# 05_-_MCU.net
KiCad netlist of a schematic drawn in Altium Designer
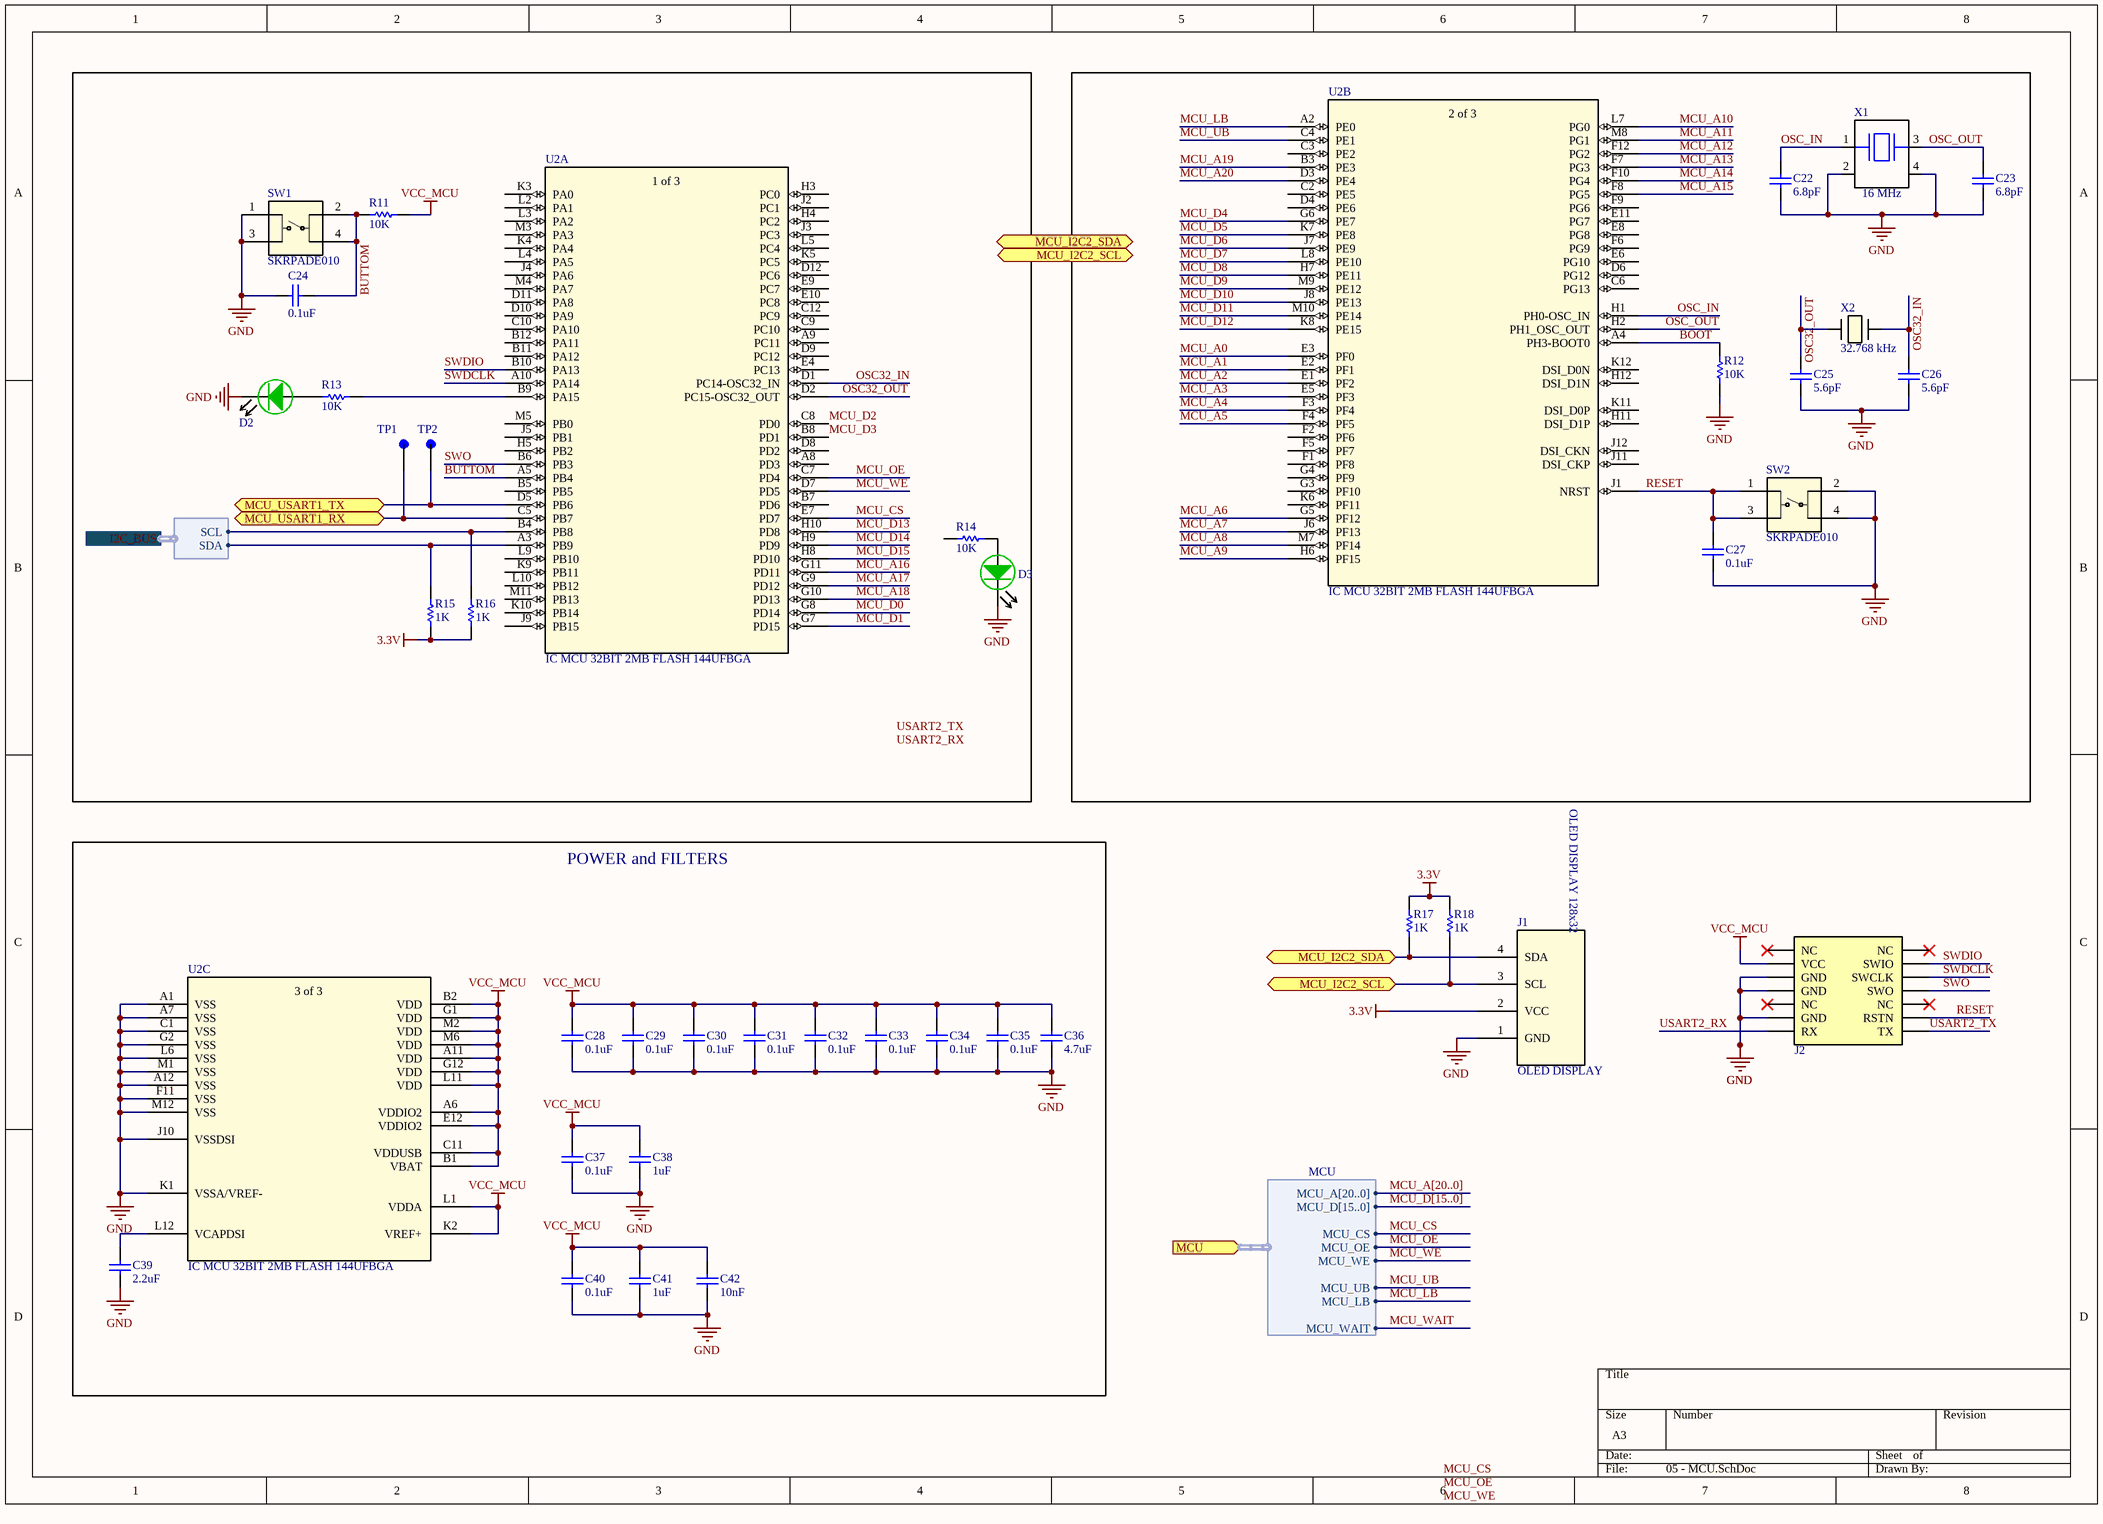
[diagram p0: 05 - MCU.SchDoc]

(export (version "E")
  (design (tool "Eeschema 10.0.6"))
  (components
    (comp (ref "C22")
      (value "6.8pF")
      (footprint "0402-C-R")
      (description "6.8 pF ±0.25pF 25V Ceramic Capacitor C0G, NP0 01005 (0402 Metric)")
      (fields (field (name "VOLTAGE") "25V") (field (name "TOLERANCE") "5%"))
      (libsource (lib "Schlib") (part "CAP CER 6.8PF 25V C0G/NP0 01005"))
    )
    (comp (ref "C23")
      (value "6.8pF")
      (footprint "0402-C-R")
      (description "6.8 pF ±0.25pF 25V Ceramic Capacitor C0G, NP0 01005 (0402 Metric)")
      (fields (field (name "VOLTAGE") "25V") (field (name "TOLERANCE") "5%"))
      (libsource (lib "Schlib") (part "CAP CER 6.8PF 25V C0G/NP0 01005"))
    )
    (comp (ref "C24")
      (value "0.1uF")
      (footprint "0402-C-R")
      (description "0.1 µF ±10% 25V Ceramic Capacitor X5R 0402 (1005 Metric)")
      (fields (field (name "VOLTAGE") "25V") (field (name "TOLERANCE") "10%"))
      (libsource (lib "Schlib") (part "CAP CER 0.1UF 25V X5R 0402"))
    )
    (comp (ref "C25")
      (value "5.6pF")
      (footprint "0402-C-R")
      (description "5.6 pF ±0.1pF 50V Ceramic Capacitor C0G, NP0 0402 (1005 Metric)")
      (fields (field (name "VOLTAGE") "50V") (field (name "TOLERANCE") "1%"))
      (libsource (lib "Schlib") (part "CAP CER 5.6PF 50V C0G/NPO 0402"))
    )
    (comp (ref "C26")
      (value "5.6pF")
      (footprint "0402-C-R")
      (description "5.6 pF ±0.1pF 50V Ceramic Capacitor C0G, NP0 0402 (1005 Metric)")
      (fields (field (name "VOLTAGE") "50V") (field (name "TOLERANCE") "1%"))
      (libsource (lib "Schlib") (part "CAP CER 5.6PF 50V C0G/NPO 0402"))
    )
    (comp (ref "C27")
      (value "0.1uF")
      (footprint "0402-C-R")
      (description "0.1 µF ±10% 25V Ceramic Capacitor X5R 0402 (1005 Metric)")
      (fields (field (name "VOLTAGE") "25V") (field (name "TOLERANCE") "10%"))
      (libsource (lib "Schlib") (part "CAP CER 0.1UF 25V X5R 0402"))
    )
    (comp (ref "C28")
      (value "0.1uF")
      (footprint "0402-C-R")
      (description "0.1 µF ±10% 25V Ceramic Capacitor X5R 0402 (1005 Metric)")
      (fields (field (name "VOLTAGE") "25V") (field (name "TOLERANCE") "10%"))
      (libsource (lib "Schlib") (part "CAP CER 0.1UF 25V X5R 0402"))
    )
    (comp (ref "C29")
      (value "0.1uF")
      (footprint "0402-C-R")
      (description "0.1 µF ±10% 25V Ceramic Capacitor X5R 0402 (1005 Metric)")
      (fields (field (name "VOLTAGE") "25V") (field (name "TOLERANCE") "10%"))
      (libsource (lib "Schlib") (part "CAP CER 0.1UF 25V X5R 0402"))
    )
    (comp (ref "C30")
      (value "0.1uF")
      (footprint "0402-C-R")
      (description "0.1 µF ±10% 25V Ceramic Capacitor X5R 0402 (1005 Metric)")
      (fields (field (name "VOLTAGE") "25V") (field (name "TOLERANCE") "10%"))
      (libsource (lib "Schlib") (part "CAP CER 0.1UF 25V X5R 0402"))
    )
    (comp (ref "C31")
      (value "0.1uF")
      (footprint "0402-C-R")
      (description "0.1 µF ±10% 25V Ceramic Capacitor X5R 0402 (1005 Metric)")
      (fields (field (name "VOLTAGE") "25V") (field (name "TOLERANCE") "10%"))
      (libsource (lib "Schlib") (part "CAP CER 0.1UF 25V X5R 0402"))
    )
    (comp (ref "C32")
      (value "0.1uF")
      (footprint "0402-C-R")
      (description "0.1 µF ±10% 25V Ceramic Capacitor X5R 0402 (1005 Metric)")
      (fields (field (name "VOLTAGE") "25V") (field (name "TOLERANCE") "10%"))
      (libsource (lib "Schlib") (part "CAP CER 0.1UF 25V X5R 0402"))
    )
    (comp (ref "C33")
      (value "0.1uF")
      (footprint "0402-C-R")
      (description "0.1 µF ±10% 25V Ceramic Capacitor X5R 0402 (1005 Metric)")
      (fields (field (name "VOLTAGE") "25V") (field (name "TOLERANCE") "10%"))
      (libsource (lib "Schlib") (part "CAP CER 0.1UF 25V X5R 0402"))
    )
    (comp (ref "C34")
      (value "0.1uF")
      (footprint "0402-C-R")
      (description "0.1 µF ±10% 25V Ceramic Capacitor X5R 0402 (1005 Metric)")
      (fields (field (name "VOLTAGE") "25V") (field (name "TOLERANCE") "10%"))
      (libsource (lib "Schlib") (part "CAP CER 0.1UF 25V X5R 0402"))
    )
    (comp (ref "C35")
      (value "0.1uF")
      (footprint "0402-C-R")
      (description "0.1 µF ±10% 25V Ceramic Capacitor X5R 0402 (1005 Metric)")
      (fields (field (name "VOLTAGE") "25V") (field (name "TOLERANCE") "10%"))
      (libsource (lib "Schlib") (part "CAP CER 0.1UF 25V X5R 0402"))
    )
    (comp (ref "C36")
      (value "4.7uF")
      (footprint "0402-C-R")
      (description "CAP SMD 0402 MLCC GERAL 4.7uF 25V ±20% 0402 X5s PN: GRM155D81C475ME15J MURATA")
      (fields (field (name "VOLTAGE") "25V") (field (name "TOLERANCE") "20%"))
      (libsource (lib "Schlib") (part "CAP CER 4.7UF 25V X5R 0402"))
    )
    (comp (ref "C37")
      (value "0.1uF")
      (footprint "0402-C-R")
      (description "0.1 µF ±10% 25V Ceramic Capacitor X5R 0402 (1005 Metric)")
      (fields (field (name "VOLTAGE") "25V") (field (name "TOLERANCE") "10%"))
      (libsource (lib "Schlib") (part "CAP CER 0.1UF 25V X5R 0402"))
    )
    (comp (ref "C38")
      (value "1uF")
      (footprint "0402-C-R")
      (description "1 µF ±10% 6.3V Ceramic Capacitor X5R 0402 (1005 Metric)")
      (fields (field (name "VOLTAGE") "6.3V") (field (name "TOLERANCE") "10%"))
      (libsource (lib "Schlib") (part "CAP CER 1UF 6.3V X5R 0402"))
    )
    (comp (ref "C39")
      (value "2.2uF")
      (footprint "0402-C-R")
      (description "2.2 µF ±20% 10V Ceramic Capacitor X5R 0402 (1005 Metric)")
      (fields (field (name "VOLTAGE") "10V") (field (name "TOLERANCE") "20%"))
      (libsource (lib "Schlib") (part "CAP CER 2.2UF 10V X5R 0402"))
    )
    (comp (ref "C40")
      (value "0.1uF")
      (footprint "0402-C-R")
      (description "0.1 µF ±10% 25V Ceramic Capacitor X5R 0402 (1005 Metric)")
      (fields (field (name "VOLTAGE") "25V") (field (name "TOLERANCE") "10%"))
      (libsource (lib "Schlib") (part "CAP CER 0.1UF 25V X5R 0402"))
    )
    (comp (ref "C41")
      (value "1uF")
      (footprint "0402-C-R")
      (description "1 µF ±10% 6.3V Ceramic Capacitor X5R 0402 (1005 Metric)")
      (fields (field (name "VOLTAGE") "6.3V") (field (name "TOLERANCE") "10%"))
      (libsource (lib "Schlib") (part "CAP CER 1UF 6.3V X5R 0402"))
    )
    (comp (ref "C42")
      (value "10nF")
      (footprint "0402-C-R")
      (description "10000 pF ±10% 25V Ceramic Capacitor X7R 0402 (1005 Metric)")
      (fields (field (name "VOLTAGE") "25V") (field (name "TOLERANCE") "10%"))
      (libsource (lib "Schlib") (part "CAP CER 10nF 25V X7R 0402"))
    )
    (comp (ref "D2")
      (value "150060GS75000")
      (footprint "LED0603")
      (description "LED SMD VD ALTO BRILHO 1,6x0,8x0,8mm 430mcd PN:150060GS75000 0603 WURTH")
      (libsource (lib "Schlib") (part "LED SMD VD 0603"))
    )
    (comp (ref "D3")
      (value "150060GS75000")
      (footprint "LED0603")
      (description "LED SMD VD ALTO BRILHO 1,6x0,8x0,8mm 430mcd PN:150060GS75000 0603 WURTH")
      (libsource (lib "Schlib") (part "LED SMD VD 0603"))
    )
    (comp (ref "J1")
      (value "OLED DISPLAY")
      (footprint "OLED_DISPLAY")
      (libsource (lib "Schlib") (part "OLED DISPLAY"))
    )
    (comp (ref "J2")
      (value "CONN HEADER SMD 14POS 1.27MM_1")
      (footprint "SAMTEC_FTSH-107-01-L-DV-K-A")
      (description "CONN HEADER SMD 14POS 1.27MM PN: FTSH-107-01-L-DV-K-A")
      (fields (field (name "MF") "Samtec Inc."))
      (libsource (lib "Schlib") (part "CONN HEADER SMD 14POS 1.27MM_1"))
    )
    (comp (ref "R11")
      (value "10K")
      (footprint "0402-R-R")
      (description "10 kOhms ±1% 0,063W, 1/16W Resistor de chip 0402 (métrico 1005) Resistente à umidade Filme grosso")
      (fields (field (name "POWER") "0.063W") (field (name "TOLERANCE") "1%"))
      (libsource (lib "Schlib") (part "RES 10K OHM 1% 1/16W 0402"))
    )
    (comp (ref "R12")
      (value "10K")
      (footprint "0402-R-R")
      (description "10 kOhms ±1% 0,063W, 1/16W Resistor de chip 0402 (métrico 1005) Resistente à umidade Filme grosso")
      (fields (field (name "POWER") "0.063W") (field (name "TOLERANCE") "1%"))
      (libsource (lib "Schlib") (part "RES 10K OHM 1% 1/16W 0402"))
    )
    (comp (ref "R13")
      (value "10K")
      (footprint "0402-R-R")
      (description "10 kOhms ±1% 0,063W, 1/16W Resistor de chip 0402 (métrico 1005) Resistente à umidade Filme grosso")
      (fields (field (name "POWER") "0.063W") (field (name "TOLERANCE") "1%"))
      (libsource (lib "Schlib") (part "RES 10K OHM 1% 1/16W 0402"))
    )
    (comp (ref "R14")
      (value "10K")
      (footprint "0402-R-R")
      (description "10 kOhms ±1% 0,063W, 1/16W Resistor de chip 0402 (métrico 1005) Resistente à umidade Filme grosso")
      (fields (field (name "POWER") "0.063W") (field (name "TOLERANCE") "1%"))
      (libsource (lib "Schlib") (part "RES 10K OHM 1% 1/16W 0402"))
    )
    (comp (ref "R15")
      (value "1K")
      (footprint "0402-R-R")
      (description "1 kOhms ±1% 0.063W, 1/16W Chip Resistor 0402 (1005 Metric) Moisture Resistant Thick Film")
      (fields (field (name "POWER") "0.063W") (field (name "TOLERANCE") "1%"))
      (libsource (lib "Schlib") (part "RES 1K OHM 1% 1/16W 0402"))
    )
    (comp (ref "R16")
      (value "1K")
      (footprint "0402-R-R")
      (description "1 kOhms ±1% 0.063W, 1/16W Chip Resistor 0402 (1005 Metric) Moisture Resistant Thick Film")
      (fields (field (name "POWER") "0.063W") (field (name "TOLERANCE") "1%"))
      (libsource (lib "Schlib") (part "RES 1K OHM 1% 1/16W 0402"))
    )
    (comp (ref "R17")
      (value "1K")
      (footprint "0402-R-R")
      (description "1 kOhms ±1% 0.063W, 1/16W Chip Resistor 0402 (1005 Metric) Moisture Resistant Thick Film")
      (fields (field (name "POWER") "0.063W") (field (name "TOLERANCE") "1%"))
      (libsource (lib "Schlib") (part "RES 1K OHM 1% 1/16W 0402"))
    )
    (comp (ref "R18")
      (value "1K")
      (footprint "0402-R-R")
      (description "1 kOhms ±1% 0.063W, 1/16W Chip Resistor 0402 (1005 Metric) Moisture Resistant Thick Film")
      (fields (field (name "POWER") "0.063W") (field (name "TOLERANCE") "1%"))
      (libsource (lib "Schlib") (part "RES 1K OHM 1% 1/16W 0402"))
    )
    (comp (ref "SW1")
      (value "SKRPADE010")
      (footprint "SKRPADE010_AAL")
      (description "Interruptor tátil SPST-NA Top atuado Montagem em superfície")
      (libsource (lib "Schlib") (part "SWITCH TACTILE SPST-NO 0.05A 16V"))
    )
    (comp (ref "SW2")
      (value "SKRPADE010")
      (footprint "SKRPADE010_AAL")
      (description "Interruptor tátil SPST-NA Top atuado Montagem em superfície")
      (libsource (lib "Schlib") (part "SWITCH TACTILE SPST-NO 0.05A 16V"))
    )
    (comp (ref "TP1")
      (value "5001")
      (footprint "TEST_POINT")
      (description "PC TEST POINT MINIATURE BLACK PN: 5001")
      (fields (field (name "MF") "Keystone Electronics Corp."))
      (libsource (lib "Schlib") (part "PC TEST POINT MINIATURE BLACK"))
    )
    (comp (ref "TP2")
      (value "5001")
      (footprint "TEST_POINT")
      (description "PC TEST POINT MINIATURE BLACK PN: 5001")
      (fields (field (name "MF") "Keystone Electronics Corp."))
      (libsource (lib "Schlib") (part "PC TEST POINT MINIATURE BLACK"))
    )
    (comp (ref "U2")
      (value "IC MCU 32BIT 2MB FLASH 144UFBGA")
      (footprint "UFBGA144-10x10mm")
      (libsource (lib "Schlib") (part "IC MCU 32BIT 2MB FLASH 144UFBGA"))
    )
    (comp (ref "X1")
      (value "16 MHz")
      (footprint "XTAL_ECS-160-8-33Q-JES-TR")
      (description "16 MHz ±20ppm Crystal 8pF 80 Ohms 4-SMD, No Lead")
      (fields (field (name "Comment") "STDCRG1-16M"))
      (libsource (lib "Schlib") (part "CRYSTAL 16.0000MHZ 8PF SMD"))
    )
    (comp (ref "X2")
      (value "32.768 kHz")
      (footprint "XTAL_NX3215SA_NDK-M - duplicate")
      (description "32.768 kHz ±20ppm Crystal 6pF 70 kOhms 2-SMD, No Lead")
      (fields (field (name "Comment") "STDMUA14-32.768K"))
      (libsource (lib "Schlib") (part "CRYSTAL 32.7680KHZ 6PF SMD"))
    )
  )
  (nets
    (net (code "3") (name "/BOOT") (class "Default")
      (node (ref "R12") (pin "2") (pinfunction "2_2") (pintype "passive"))
      (node (ref "U2") (pin "A4") (pinfunction "PH3-BOOT0_A4") (pintype "bidirectional"))
    )
    (net (code "4") (name "/BUTTOM") (class "Default")
      (node (ref "C24") (pin "1") (pinfunction "1_1") (pintype "passive"))
      (node (ref "R11") (pin "2") (pinfunction "2_2") (pintype "passive"))
      (node (ref "SW1") (pin "2") (pinfunction "2_2") (pintype "passive"))
      (node (ref "SW1") (pin "4") (pinfunction "4_4") (pintype "passive"))
      (node (ref "U2") (pin "A5") (pinfunction "PB4_A5") (pintype "bidirectional"))
    )
    (net (code "5") (name "/MCU_A0") (class "Default")
      (node (ref "U2") (pin "E3") (pinfunction "PF0_E3") (pintype "bidirectional"))
    )
    (net (code "6") (name "/MCU_A1") (class "Default")
      (node (ref "U2") (pin "E2") (pinfunction "PF1_E2") (pintype "bidirectional"))
    )
    (net (code "7") (name "/MCU_A2") (class "Default")
      (node (ref "U2") (pin "E1") (pinfunction "PF2_E1") (pintype "bidirectional"))
    )
    (net (code "8") (name "/MCU_A3") (class "Default")
      (node (ref "U2") (pin "E5") (pinfunction "PF3_E5") (pintype "bidirectional"))
    )
    (net (code "9") (name "/MCU_A4") (class "Default")
      (node (ref "U2") (pin "F3") (pinfunction "PF4_F3") (pintype "bidirectional"))
    )
    (net (code "10") (name "/MCU_A5") (class "Default")
      (node (ref "U2") (pin "F4") (pinfunction "PF5_F4") (pintype "bidirectional"))
    )
    (net (code "11") (name "/MCU_A6") (class "Default")
      (node (ref "U2") (pin "G5") (pinfunction "PF12_G5") (pintype "bidirectional"))
    )
    (net (code "12") (name "/MCU_A7") (class "Default")
      (node (ref "U2") (pin "J6") (pinfunction "PF13_J6") (pintype "bidirectional"))
    )
    (net (code "13") (name "/MCU_A8") (class "Default")
      (node (ref "U2") (pin "M7") (pinfunction "PF14_M7") (pintype "bidirectional"))
    )
    (net (code "14") (name "/MCU_A9") (class "Default")
      (node (ref "U2") (pin "H6") (pinfunction "PF15_H6") (pintype "bidirectional"))
    )
    (net (code "15") (name "/MCU_A10") (class "Default")
      (node (ref "U2") (pin "L7") (pinfunction "PG0_L7") (pintype "bidirectional"))
    )
    (net (code "16") (name "/MCU_A11") (class "Default")
      (node (ref "U2") (pin "M8") (pinfunction "PG1_M8") (pintype "bidirectional"))
    )
    (net (code "17") (name "/MCU_A12") (class "Default")
      (node (ref "U2") (pin "F12") (pinfunction "PG2_F12") (pintype "bidirectional"))
    )
    (net (code "18") (name "/MCU_A13") (class "Default")
      (node (ref "U2") (pin "F7") (pinfunction "PG3_F7") (pintype "bidirectional"))
    )
    (net (code "19") (name "/MCU_A14") (class "Default")
      (node (ref "U2") (pin "F10") (pinfunction "PG4_F10") (pintype "bidirectional"))
    )
    (net (code "20") (name "/MCU_A15") (class "Default")
      (node (ref "U2") (pin "F8") (pinfunction "PG5_F8") (pintype "bidirectional"))
    )
    (net (code "21") (name "/MCU_A16") (class "Default")
      (node (ref "U2") (pin "G11") (pinfunction "PD11_G11") (pintype "bidirectional"))
    )
    (net (code "22") (name "/MCU_A17") (class "Default")
      (node (ref "U2") (pin "G9") (pinfunction "PD12_G9") (pintype "bidirectional"))
    )
    (net (code "23") (name "/MCU_A18") (class "Default")
      (node (ref "U2") (pin "G10") (pinfunction "PD13_G10") (pintype "bidirectional"))
    )
    (net (code "24") (name "/MCU_A19") (class "Default")
      (node (ref "U2") (pin "B3") (pinfunction "PE3_B3") (pintype "bidirectional"))
    )
    (net (code "25") (name "/MCU_A20") (class "Default")
      (node (ref "U2") (pin "D3") (pinfunction "PE4_D3") (pintype "bidirectional"))
    )
    (net (code "26") (name "/MCU_CS") (class "Default")
      (node (ref "U2") (pin "E7") (pinfunction "PD7_E7") (pintype "bidirectional"))
    )
    (net (code "27") (name "/MCU_D0") (class "Default")
      (node (ref "U2") (pin "G8") (pinfunction "PD14_G8") (pintype "bidirectional"))
    )
    (net (code "28") (name "/MCU_D1") (class "Default")
      (node (ref "U2") (pin "G7") (pinfunction "PD15_G7") (pintype "bidirectional"))
    )
    (net (code "29") (name "/MCU_D2") (class "Default")
      (node (ref "U2") (pin "C8") (pinfunction "PD0_C8") (pintype "bidirectional"))
    )
    (net (code "30") (name "/MCU_D3") (class "Default")
      (node (ref "U2") (pin "B8") (pinfunction "PD1_B8") (pintype "bidirectional"))
    )
    (net (code "31") (name "/MCU_D4") (class "Default")
      (node (ref "U2") (pin "G6") (pinfunction "PE7_G6") (pintype "bidirectional"))
    )
    (net (code "32") (name "/MCU_D5") (class "Default")
      (node (ref "U2") (pin "K7") (pinfunction "PE8_K7") (pintype "bidirectional"))
    )
    (net (code "33") (name "/MCU_D6") (class "Default")
      (node (ref "U2") (pin "J7") (pinfunction "PE9_J7") (pintype "bidirectional"))
    )
    (net (code "34") (name "/MCU_D7") (class "Default")
      (node (ref "U2") (pin "L8") (pinfunction "PE10_L8") (pintype "bidirectional"))
    )
    (net (code "35") (name "/MCU_D8") (class "Default")
      (node (ref "U2") (pin "H7") (pinfunction "PE11_H7") (pintype "bidirectional"))
    )
    (net (code "36") (name "/MCU_D9") (class "Default")
      (node (ref "U2") (pin "M9") (pinfunction "PE12_M9") (pintype "bidirectional"))
    )
    (net (code "37") (name "/MCU_D10") (class "Default")
      (node (ref "U2") (pin "J8") (pinfunction "PE13_J8") (pintype "bidirectional"))
    )
    (net (code "38") (name "/MCU_D11") (class "Default")
      (node (ref "U2") (pin "M10") (pinfunction "PE14_M10") (pintype "bidirectional"))
    )
    (net (code "39") (name "/MCU_D12") (class "Default")
      (node (ref "U2") (pin "K8") (pinfunction "PE15_K8") (pintype "bidirectional"))
    )
    (net (code "40") (name "/MCU_D13") (class "Default")
      (node (ref "U2") (pin "H10") (pinfunction "PD8_H10") (pintype "bidirectional"))
    )
    (net (code "41") (name "/MCU_D14") (class "Default")
      (node (ref "U2") (pin "H9") (pinfunction "PD9_H9") (pintype "bidirectional"))
    )
    (net (code "42") (name "/MCU_D15") (class "Default")
      (node (ref "U2") (pin "H8") (pinfunction "PD10_H8") (pintype "bidirectional"))
    )
    (net (code "44") (name "/MCU_I2C2_SCL") (class "Default")
      (node (ref "J1") (pin "3") (pinfunction "SCL_3") (pintype "passive"))
      (node (ref "R18") (pin "1") (pinfunction "1_1") (pintype "passive"))
    )
    (net (code "45") (name "/MCU_I2C2_SDA") (class "Default")
      (node (ref "J1") (pin "4") (pinfunction "SDA_4") (pintype "passive"))
      (node (ref "R17") (pin "1") (pinfunction "1_1") (pintype "passive"))
    )
    (net (code "46") (name "/MCU_LB") (class "Default")
      (node (ref "U2") (pin "A2") (pinfunction "PE0_A2") (pintype "bidirectional"))
    )
    (net (code "47") (name "/MCU_OE") (class "Default")
      (node (ref "U2") (pin "C7") (pinfunction "PD4_C7") (pintype "bidirectional"))
    )
    (net (code "48") (name "/MCU_UB") (class "Default")
      (node (ref "U2") (pin "C4") (pinfunction "PE1_C4") (pintype "bidirectional"))
    )
    (net (code "49") (name "/MCU_USART1_RX") (class "Default")
      (node (ref "TP1") (pin "1") (pintype "passive"))
      (node (ref "U2") (pin "C5") (pinfunction "PB7_C5") (pintype "bidirectional"))
    )
    (net (code "50") (name "/MCU_USART1_TX") (class "Default")
      (node (ref "TP2") (pin "1") (pintype "passive"))
      (node (ref "U2") (pin "D5") (pinfunction "PB6_D5") (pintype "bidirectional"))
    )
    (net (code "52") (name "/MCU_WE") (class "Default")
      (node (ref "U2") (pin "D7") (pinfunction "PD5_D7") (pintype "bidirectional"))
    )
    (net (code "54") (name "/OSC32_IN") (class "Default")
      (node (ref "C26") (pin "1") (pinfunction "1_1") (pintype "passive"))
      (node (ref "U2") (pin "D1") (pinfunction "PC14-OSC32_IN_D1") (pintype "bidirectional"))
      (node (ref "X2") (pin "2") (pinfunction "2_2") (pintype "passive"))
    )
    (net (code "55") (name "/OSC32_OUT") (class "Default")
      (node (ref "C25") (pin "1") (pinfunction "1_1") (pintype "passive"))
      (node (ref "U2") (pin "D2") (pinfunction "PC15-OSC32_OUT_D2") (pintype "bidirectional"))
      (node (ref "X2") (pin "1") (pinfunction "1_1") (pintype "passive"))
    )
    (net (code "56") (name "/OSC_IN") (class "Default")
      (node (ref "C22") (pin "2") (pinfunction "2_2") (pintype "passive"))
      (node (ref "U2") (pin "H1") (pinfunction "PH0-OSC_IN_H1") (pintype "bidirectional"))
      (node (ref "X1") (pin "1") (pinfunction "1_1") (pintype "passive"))
    )
    (net (code "57") (name "/OSC_OUT") (class "Default")
      (node (ref "C23") (pin "1") (pinfunction "1_1") (pintype "passive"))
      (node (ref "U2") (pin "H2") (pinfunction "PH1_OSC_OUT_H2") (pintype "bidirectional"))
      (node (ref "X1") (pin "3") (pinfunction "2_3") (pintype "passive"))
    )
    (net (code "58") (name "/RESET") (class "Default")
      (node (ref "C27") (pin "2") (pinfunction "2_2") (pintype "passive"))
      (node (ref "J2") (pin "12") (pinfunction "RSTN_12") (pintype "passive"))
      (node (ref "SW2") (pin "1") (pinfunction "1_1") (pintype "passive"))
      (node (ref "SW2") (pin "3") (pinfunction "3_3") (pintype "passive"))
      (node (ref "U2") (pin "J1") (pinfunction "NRST_J1") (pintype "bidirectional"))
    )
    (net (code "59") (name "/SWDCLK") (class "Default")
      (node (ref "J2") (pin "06") (pinfunction "SWCLK_06") (pintype "passive"))
      (node (ref "U2") (pin "A10") (pinfunction "PA14_A10") (pintype "bidirectional"))
    )
    (net (code "60") (name "/SWDIO") (class "Default")
      (node (ref "J2") (pin "04") (pinfunction "SWIO_04") (pintype "passive"))
      (node (ref "U2") (pin "B10") (pinfunction "PA13_B10") (pintype "bidirectional"))
    )
    (net (code "61") (name "/SWO") (class "Default")
      (node (ref "J2") (pin "08") (pinfunction "SWO_08") (pintype "passive"))
      (node (ref "U2") (pin "B6") (pinfunction "PB3_B6") (pintype "bidirectional"))
    )
    (net (code "62") (name "/USART2_RX") (class "Default")
      (node (ref "J2") (pin "13") (pinfunction "RX_13") (pintype "passive"))
    )
    (net (code "63") (name "/USART2_TX") (class "Default")
      (node (ref "J2") (pin "14") (pinfunction "TX_14") (pintype "passive"))
    )
    (net (code "66") (name "3.3V") (class "Default")
      (node (ref "J1") (pin "2") (pinfunction "VCC_2") (pintype "passive"))
      (node (ref "R15") (pin "2") (pinfunction "2_2") (pintype "passive"))
      (node (ref "R16") (pin "2") (pinfunction "2_2") (pintype "passive"))
      (node (ref "R17") (pin "2") (pinfunction "2_2") (pintype "passive"))
      (node (ref "R18") (pin "2") (pinfunction "2_2") (pintype "passive"))
    )
    (net (code "67") (name "GND") (class "Default")
      (node (ref "C22") (pin "1") (pinfunction "1_1") (pintype "passive"))
      (node (ref "C23") (pin "2") (pinfunction "2_2") (pintype "passive"))
      (node (ref "C24") (pin "2") (pinfunction "2_2") (pintype "passive"))
      (node (ref "C25") (pin "2") (pinfunction "2_2") (pintype "passive"))
      (node (ref "C26") (pin "2") (pinfunction "2_2") (pintype "passive"))
      (node (ref "C27") (pin "1") (pinfunction "1_1") (pintype "passive"))
      (node (ref "C28") (pin "1") (pinfunction "1_1") (pintype "passive"))
      (node (ref "C29") (pin "1") (pinfunction "1_1") (pintype "passive"))
      (node (ref "C30") (pin "1") (pinfunction "1_1") (pintype "passive"))
      (node (ref "C31") (pin "1") (pinfunction "1_1") (pintype "passive"))
      (node (ref "C32") (pin "1") (pinfunction "1_1") (pintype "passive"))
      (node (ref "C33") (pin "1") (pinfunction "1_1") (pintype "passive"))
      (node (ref "C34") (pin "1") (pinfunction "1_1") (pintype "passive"))
      (node (ref "C35") (pin "1") (pinfunction "1_1") (pintype "passive"))
      (node (ref "C36") (pin "1") (pinfunction "1_1") (pintype "passive"))
      (node (ref "C37") (pin "1") (pinfunction "1_1") (pintype "passive"))
      (node (ref "C38") (pin "1") (pinfunction "1_1") (pintype "passive"))
      (node (ref "C39") (pin "1") (pinfunction "1_1") (pintype "passive"))
      (node (ref "C40") (pin "1") (pinfunction "1_1") (pintype "passive"))
      (node (ref "C41") (pin "1") (pinfunction "1_1") (pintype "passive"))
      (node (ref "C42") (pin "1") (pinfunction "1_1") (pintype "passive"))
      (node (ref "D2") (pin "1") (pinfunction "K_1") (pintype "passive"))
      (node (ref "D3") (pin "1") (pinfunction "K_1") (pintype "passive"))
      (node (ref "J1") (pin "1") (pinfunction "GND_1") (pintype "passive"))
      (node (ref "J2") (pin "05") (pinfunction "GND_05") (pintype "passive"))
      (node (ref "J2") (pin "07") (pinfunction "GND_07") (pintype "passive"))
      (node (ref "J2") (pin "11") (pinfunction "GND_11") (pintype "passive"))
      (node (ref "R12") (pin "1") (pinfunction "1_1") (pintype "passive"))
      (node (ref "SW1") (pin "1") (pinfunction "1_1") (pintype "passive"))
      (node (ref "SW1") (pin "3") (pinfunction "3_3") (pintype "passive"))
      (node (ref "SW2") (pin "2") (pinfunction "2_2") (pintype "passive"))
      (node (ref "SW2") (pin "4") (pinfunction "4_4") (pintype "passive"))
      (node (ref "U2") (pin "A1") (pinfunction "VSS_A1") (pintype "power_in"))
      (node (ref "U2") (pin "A12") (pinfunction "VSS_A12") (pintype "power_in"))
      (node (ref "U2") (pin "A7") (pinfunction "VSS_A7") (pintype "power_in"))
      (node (ref "U2") (pin "C1") (pinfunction "VSS_C1") (pintype "power_in"))
      (node (ref "U2") (pin "F11") (pinfunction "VSS_F11") (pintype "power_in"))
      (node (ref "U2") (pin "G2") (pinfunction "VSS_G2") (pintype "power_in"))
      (node (ref "U2") (pin "J10") (pinfunction "VSSDSI_J10") (pintype "power_in"))
      (node (ref "U2") (pin "K1") (pinfunction "VSSA/VREF-_K1") (pintype "power_in"))
      (node (ref "U2") (pin "L6") (pinfunction "VSS_L6") (pintype "power_in"))
      (node (ref "U2") (pin "M1") (pinfunction "VSS_M1") (pintype "power_in"))
      (node (ref "U2") (pin "M12") (pinfunction "VSS_M12") (pintype "power_in"))
      (node (ref "X1") (pin "2") (pinfunction "GND_2") (pintype "power_in"))
      (node (ref "X1") (pin "4") (pinfunction "GND_4") (pintype "power_in"))
    )
    (net (code "68") (name "Net-(D2-A)") (class "Default")
      (node (ref "D2") (pin "2") (pinfunction "A_2") (pintype "passive"))
      (node (ref "R13") (pin "2") (pinfunction "2_2") (pintype "passive"))
    )
    (net (code "69") (name "Net-(D3-A)") (class "Default")
      (node (ref "D3") (pin "2") (pinfunction "A_2") (pintype "passive"))
      (node (ref "R14") (pin "1") (pinfunction "1_1") (pintype "passive"))
    )
    (net (code "70") (name "Net-(U2A-PA15)") (class "Default")
      (node (ref "R13") (pin "1") (pinfunction "1_1") (pintype "passive"))
      (node (ref "U2") (pin "B9") (pinfunction "PA15_B9") (pintype "bidirectional"))
    )
    (net (code "71") (name "Net-(U2A-PB8)") (class "Default")
      (node (ref "R16") (pin "1") (pinfunction "1_1") (pintype "passive"))
      (node (ref "U2") (pin "B4") (pinfunction "PB8_B4") (pintype "bidirectional"))
    )
    (net (code "72") (name "Net-(U2A-PB9)") (class "Default")
      (node (ref "R15") (pin "1") (pinfunction "1_1") (pintype "passive"))
      (node (ref "U2") (pin "A3") (pinfunction "PB9_A3") (pintype "bidirectional"))
    )
    (net (code "73") (name "Net-(U2C-VCAPDSI)") (class "Default")
      (node (ref "C39") (pin "2") (pinfunction "2_2") (pintype "passive"))
      (node (ref "U2") (pin "L12") (pinfunction "VCAPDSI_L12") (pintype "power_in"))
    )
    (net (code "74") (name "VCC_MCU") (class "Default")
      (node (ref "C28") (pin "2") (pinfunction "2_2") (pintype "passive"))
      (node (ref "C29") (pin "2") (pinfunction "2_2") (pintype "passive"))
      (node (ref "C30") (pin "2") (pinfunction "2_2") (pintype "passive"))
      (node (ref "C31") (pin "2") (pinfunction "2_2") (pintype "passive"))
      (node (ref "C32") (pin "2") (pinfunction "2_2") (pintype "passive"))
      (node (ref "C33") (pin "2") (pinfunction "2_2") (pintype "passive"))
      (node (ref "C34") (pin "2") (pinfunction "2_2") (pintype "passive"))
      (node (ref "C35") (pin "2") (pinfunction "2_2") (pintype "passive"))
      (node (ref "C36") (pin "2") (pinfunction "2_2") (pintype "passive"))
      (node (ref "C37") (pin "2") (pinfunction "2_2") (pintype "passive"))
      (node (ref "C38") (pin "2") (pinfunction "2_2") (pintype "passive"))
      (node (ref "C40") (pin "2") (pinfunction "2_2") (pintype "passive"))
      (node (ref "C41") (pin "2") (pinfunction "2_2") (pintype "passive"))
      (node (ref "C42") (pin "2") (pinfunction "2_2") (pintype "passive"))
      (node (ref "J2") (pin "03") (pinfunction "VCC_03") (pintype "passive"))
      (node (ref "R11") (pin "1") (pinfunction "1_1") (pintype "passive"))
      (node (ref "U2") (pin "A11") (pinfunction "VDD_A11") (pintype "power_in"))
      (node (ref "U2") (pin "A6") (pinfunction "VDDIO2_A6") (pintype "power_in"))
      (node (ref "U2") (pin "B1") (pinfunction "VBAT_B1") (pintype "power_in"))
      (node (ref "U2") (pin "B2") (pinfunction "VDD_B2") (pintype "power_in"))
      (node (ref "U2") (pin "C11") (pinfunction "VDDUSB_C11") (pintype "power_in"))
      (node (ref "U2") (pin "E12") (pinfunction "VDDIO2_E12") (pintype "power_in"))
      (node (ref "U2") (pin "G1") (pinfunction "VDD_G1") (pintype "power_in"))
      (node (ref "U2") (pin "G12") (pinfunction "VDD_G12") (pintype "power_in"))
      (node (ref "U2") (pin "K2") (pinfunction "VREF+_K2") (pintype "power_in"))
      (node (ref "U2") (pin "L1") (pinfunction "VDDA_L1") (pintype "power_in"))
      (node (ref "U2") (pin "L11") (pinfunction "VDD_L11") (pintype "power_in"))
      (node (ref "U2") (pin "M2") (pinfunction "VDD_M2") (pintype "power_in"))
      (node (ref "U2") (pin "M6") (pinfunction "VDD_M6") (pintype "power_in"))
    )
    (net (code "75") (name "unconnected-(J2-NC-Pad01)") (class "Default")
      (node (ref "J2") (pin "01") (pinfunction "NC_01") (pintype "passive+no_connect"))
    )
    (net (code "76") (name "unconnected-(J2-NC-Pad02)") (class "Default")
      (node (ref "J2") (pin "02") (pinfunction "NC_02") (pintype "passive+no_connect"))
    )
    (net (code "77") (name "unconnected-(J2-NC-Pad09)") (class "Default")
      (node (ref "J2") (pin "09") (pinfunction "NC_09") (pintype "passive+no_connect"))
    )
    (net (code "78") (name "unconnected-(J2-NC-Pad10)") (class "Default")
      (node (ref "J2") (pin "10") (pinfunction "NC_10") (pintype "passive+no_connect"))
    )
    (net (code "79") (name "unconnected-(R14-Pad2)") (class "Default")
      (node (ref "R14") (pin "2") (pinfunction "2_2") (pintype "passive"))
    )
    (net (code "80") (name "unconnected-(U2A-PA0-PadK3)") (class "Default")
      (node (ref "U2") (pin "K3") (pinfunction "PA0_K3") (pintype "bidirectional"))
    )
    (net (code "81") (name "unconnected-(U2A-PA1-PadL2)") (class "Default")
      (node (ref "U2") (pin "L2") (pinfunction "PA1_L2") (pintype "bidirectional"))
    )
    (net (code "82") (name "unconnected-(U2A-PA2-PadL3)") (class "Default")
      (node (ref "U2") (pin "L3") (pinfunction "PA2_L3") (pintype "bidirectional"))
    )
    (net (code "83") (name "unconnected-(U2A-PA3-PadM3)") (class "Default")
      (node (ref "U2") (pin "M3") (pinfunction "PA3_M3") (pintype "bidirectional"))
    )
    (net (code "84") (name "unconnected-(U2A-PA4-PadK4)") (class "Default")
      (node (ref "U2") (pin "K4") (pinfunction "PA4_K4") (pintype "bidirectional"))
    )
    (net (code "85") (name "unconnected-(U2A-PA5-PadL4)") (class "Default")
      (node (ref "U2") (pin "L4") (pinfunction "PA5_L4") (pintype "bidirectional"))
    )
    (net (code "86") (name "unconnected-(U2A-PA6-PadJ4)") (class "Default")
      (node (ref "U2") (pin "J4") (pinfunction "PA6_J4") (pintype "bidirectional"))
    )
    (net (code "87") (name "unconnected-(U2A-PA7-PadM4)") (class "Default")
      (node (ref "U2") (pin "M4") (pinfunction "PA7_M4") (pintype "bidirectional"))
    )
    (net (code "88") (name "unconnected-(U2A-PA8-PadD11)") (class "Default")
      (node (ref "U2") (pin "D11") (pinfunction "PA8_D11") (pintype "bidirectional"))
    )
    (net (code "89") (name "unconnected-(U2A-PA9-PadD10)") (class "Default")
      (node (ref "U2") (pin "D10") (pinfunction "PA9_D10") (pintype "bidirectional"))
    )
    (net (code "90") (name "unconnected-(U2A-PA10-PadC10)") (class "Default")
      (node (ref "U2") (pin "C10") (pinfunction "PA10_C10") (pintype "bidirectional"))
    )
    (net (code "91") (name "unconnected-(U2A-PA11-PadB12)") (class "Default")
      (node (ref "U2") (pin "B12") (pinfunction "PA11_B12") (pintype "bidirectional"))
    )
    (net (code "92") (name "unconnected-(U2A-PA12-PadB11)") (class "Default")
      (node (ref "U2") (pin "B11") (pinfunction "PA12_B11") (pintype "bidirectional"))
    )
    (net (code "93") (name "unconnected-(U2A-PB0-PadM5)") (class "Default")
      (node (ref "U2") (pin "M5") (pinfunction "PB0_M5") (pintype "bidirectional"))
    )
    (net (code "94") (name "unconnected-(U2A-PB1-PadJ5)") (class "Default")
      (node (ref "U2") (pin "J5") (pinfunction "PB1_J5") (pintype "bidirectional"))
    )
    (net (code "95") (name "unconnected-(U2A-PB2-PadH5)") (class "Default")
      (node (ref "U2") (pin "H5") (pinfunction "PB2_H5") (pintype "bidirectional"))
    )
    (net (code "96") (name "unconnected-(U2A-PB5-PadB5)") (class "Default")
      (node (ref "U2") (pin "B5") (pinfunction "PB5_B5") (pintype "bidirectional"))
    )
    (net (code "97") (name "unconnected-(U2A-PB10-PadL9)") (class "Default")
      (node (ref "U2") (pin "L9") (pinfunction "PB10_L9") (pintype "bidirectional"))
    )
    (net (code "98") (name "unconnected-(U2A-PB11-PadK9)") (class "Default")
      (node (ref "U2") (pin "K9") (pinfunction "PB11_K9") (pintype "bidirectional"))
    )
    (net (code "99") (name "unconnected-(U2A-PB12-PadL10)") (class "Default")
      (node (ref "U2") (pin "L10") (pinfunction "PB12_L10") (pintype "bidirectional"))
    )
    (net (code "100") (name "unconnected-(U2A-PB13-PadM11)") (class "Default")
      (node (ref "U2") (pin "M11") (pinfunction "PB13_M11") (pintype "bidirectional"))
    )
    (net (code "101") (name "unconnected-(U2A-PB14-PadK10)") (class "Default")
      (node (ref "U2") (pin "K10") (pinfunction "PB14_K10") (pintype "bidirectional"))
    )
    (net (code "102") (name "unconnected-(U2A-PB15-PadJ9)") (class "Default")
      (node (ref "U2") (pin "J9") (pinfunction "PB15_J9") (pintype "bidirectional"))
    )
    (net (code "103") (name "unconnected-(U2A-PC0-PadH3)") (class "Default")
      (node (ref "U2") (pin "H3") (pinfunction "PC0_H3") (pintype "bidirectional"))
    )
    (net (code "104") (name "unconnected-(U2A-PC1-PadJ2)") (class "Default")
      (node (ref "U2") (pin "J2") (pinfunction "PC1_J2") (pintype "bidirectional"))
    )
    (net (code "105") (name "unconnected-(U2A-PC2-PadH4)") (class "Default")
      (node (ref "U2") (pin "H4") (pinfunction "PC2_H4") (pintype "bidirectional"))
    )
    (net (code "106") (name "unconnected-(U2A-PC3-PadJ3)") (class "Default")
      (node (ref "U2") (pin "J3") (pinfunction "PC3_J3") (pintype "bidirectional"))
    )
    (net (code "107") (name "unconnected-(U2A-PC4-PadL5)") (class "Default")
      (node (ref "U2") (pin "L5") (pinfunction "PC4_L5") (pintype "bidirectional"))
    )
    (net (code "108") (name "unconnected-(U2A-PC5-PadK5)") (class "Default")
      (node (ref "U2") (pin "K5") (pinfunction "PC5_K5") (pintype "bidirectional"))
    )
    (net (code "109") (name "unconnected-(U2A-PC6-PadD12)") (class "Default")
      (node (ref "U2") (pin "D12") (pinfunction "PC6_D12") (pintype "bidirectional"))
    )
    (net (code "110") (name "unconnected-(U2A-PC7-PadE9)") (class "Default")
      (node (ref "U2") (pin "E9") (pinfunction "PC7_E9") (pintype "bidirectional"))
    )
    (net (code "111") (name "unconnected-(U2A-PC8-PadE10)") (class "Default")
      (node (ref "U2") (pin "E10") (pinfunction "PC8_E10") (pintype "bidirectional"))
    )
    (net (code "112") (name "unconnected-(U2A-PC9-PadC12)") (class "Default")
      (node (ref "U2") (pin "C12") (pinfunction "PC9_C12") (pintype "bidirectional"))
    )
    (net (code "113") (name "unconnected-(U2A-PC10-PadC9)") (class "Default")
      (node (ref "U2") (pin "C9") (pinfunction "PC10_C9") (pintype "bidirectional"))
    )
    (net (code "114") (name "unconnected-(U2A-PC11-PadA9)") (class "Default")
      (node (ref "U2") (pin "A9") (pinfunction "PC11_A9") (pintype "bidirectional"))
    )
    (net (code "115") (name "unconnected-(U2A-PC12-PadD9)") (class "Default")
      (node (ref "U2") (pin "D9") (pinfunction "PC12_D9") (pintype "bidirectional"))
    )
    (net (code "116") (name "unconnected-(U2A-PC13-PadE4)") (class "Default")
      (node (ref "U2") (pin "E4") (pinfunction "PC13_E4") (pintype "bidirectional"))
    )
    (net (code "117") (name "unconnected-(U2A-PD2-PadD8)") (class "Default")
      (node (ref "U2") (pin "D8") (pinfunction "PD2_D8") (pintype "bidirectional"))
    )
    (net (code "118") (name "unconnected-(U2A-PD3-PadA8)") (class "Default")
      (node (ref "U2") (pin "A8") (pinfunction "PD3_A8") (pintype "bidirectional"))
    )
    (net (code "119") (name "unconnected-(U2A-PD6-PadB7)") (class "Default")
      (node (ref "U2") (pin "B7") (pinfunction "PD6_B7") (pintype "bidirectional"))
    )
    (net (code "120") (name "unconnected-(U2B-DSI_CKN-PadJ12)") (class "Default")
      (node (ref "U2") (pin "J12") (pinfunction "DSI_CKN_J12") (pintype "bidirectional"))
    )
    (net (code "121") (name "unconnected-(U2B-DSI_CKP-PadJ11)") (class "Default")
      (node (ref "U2") (pin "J11") (pinfunction "DSI_CKP_J11") (pintype "bidirectional"))
    )
    (net (code "122") (name "unconnected-(U2B-DSI_D0N-PadK12)") (class "Default")
      (node (ref "U2") (pin "K12") (pinfunction "DSI_D0N_K12") (pintype "bidirectional"))
    )
    (net (code "123") (name "unconnected-(U2B-DSI_D0P-PadK11)") (class "Default")
      (node (ref "U2") (pin "K11") (pinfunction "DSI_D0P_K11") (pintype "bidirectional"))
    )
    (net (code "124") (name "unconnected-(U2B-DSI_D1N-PadH12)") (class "Default")
      (node (ref "U2") (pin "H12") (pinfunction "DSI_D1N_H12") (pintype "bidirectional"))
    )
    (net (code "125") (name "unconnected-(U2B-DSI_D1P-PadH11)") (class "Default")
      (node (ref "U2") (pin "H11") (pinfunction "DSI_D1P_H11") (pintype "bidirectional"))
    )
    (net (code "126") (name "unconnected-(U2B-PE2-PadC3)") (class "Default")
      (node (ref "U2") (pin "C3") (pinfunction "PE2_C3") (pintype "bidirectional"))
    )
    (net (code "127") (name "unconnected-(U2B-PE5-PadC2)") (class "Default")
      (node (ref "U2") (pin "C2") (pinfunction "PE5_C2") (pintype "bidirectional"))
    )
    (net (code "128") (name "unconnected-(U2B-PE6-PadD4)") (class "Default")
      (node (ref "U2") (pin "D4") (pinfunction "PE6_D4") (pintype "bidirectional"))
    )
    (net (code "129") (name "unconnected-(U2B-PF6-PadF2)") (class "Default")
      (node (ref "U2") (pin "F2") (pinfunction "PF6_F2") (pintype "bidirectional"))
    )
    (net (code "130") (name "unconnected-(U2B-PF7-PadF5)") (class "Default")
      (node (ref "U2") (pin "F5") (pinfunction "PF7_F5") (pintype "bidirectional"))
    )
    (net (code "131") (name "unconnected-(U2B-PF8-PadF1)") (class "Default")
      (node (ref "U2") (pin "F1") (pinfunction "PF8_F1") (pintype "bidirectional"))
    )
    (net (code "132") (name "unconnected-(U2B-PF9-PadG4)") (class "Default")
      (node (ref "U2") (pin "G4") (pinfunction "PF9_G4") (pintype "bidirectional"))
    )
    (net (code "133") (name "unconnected-(U2B-PF10-PadG3)") (class "Default")
      (node (ref "U2") (pin "G3") (pinfunction "PF10_G3") (pintype "bidirectional"))
    )
    (net (code "134") (name "unconnected-(U2B-PF11-PadK6)") (class "Default")
      (node (ref "U2") (pin "K6") (pinfunction "PF11_K6") (pintype "bidirectional"))
    )
    (net (code "135") (name "unconnected-(U2B-PG6-PadF9)") (class "Default")
      (node (ref "U2") (pin "F9") (pinfunction "PG6_F9") (pintype "bidirectional"))
    )
    (net (code "136") (name "unconnected-(U2B-PG7-PadE11)") (class "Default")
      (node (ref "U2") (pin "E11") (pinfunction "PG7_E11") (pintype "bidirectional"))
    )
    (net (code "137") (name "unconnected-(U2B-PG8-PadE8)") (class "Default")
      (node (ref "U2") (pin "E8") (pinfunction "PG8_E8") (pintype "bidirectional"))
    )
    (net (code "138") (name "unconnected-(U2B-PG9-PadF6)") (class "Default")
      (node (ref "U2") (pin "F6") (pinfunction "PG9_F6") (pintype "bidirectional"))
    )
    (net (code "139") (name "unconnected-(U2B-PG10-PadE6)") (class "Default")
      (node (ref "U2") (pin "E6") (pinfunction "PG10_E6") (pintype "bidirectional"))
    )
    (net (code "140") (name "unconnected-(U2B-PG12-PadD6)") (class "Default")
      (node (ref "U2") (pin "D6") (pinfunction "PG12_D6") (pintype "bidirectional"))
    )
    (net (code "141") (name "unconnected-(U2B-PG13-PadC6)") (class "Default")
      (node (ref "U2") (pin "C6") (pinfunction "PG13_C6") (pintype "bidirectional"))
    )
  )
)
